# POWER.net
KiCad netlist of a schematic drawn in Altium Designer
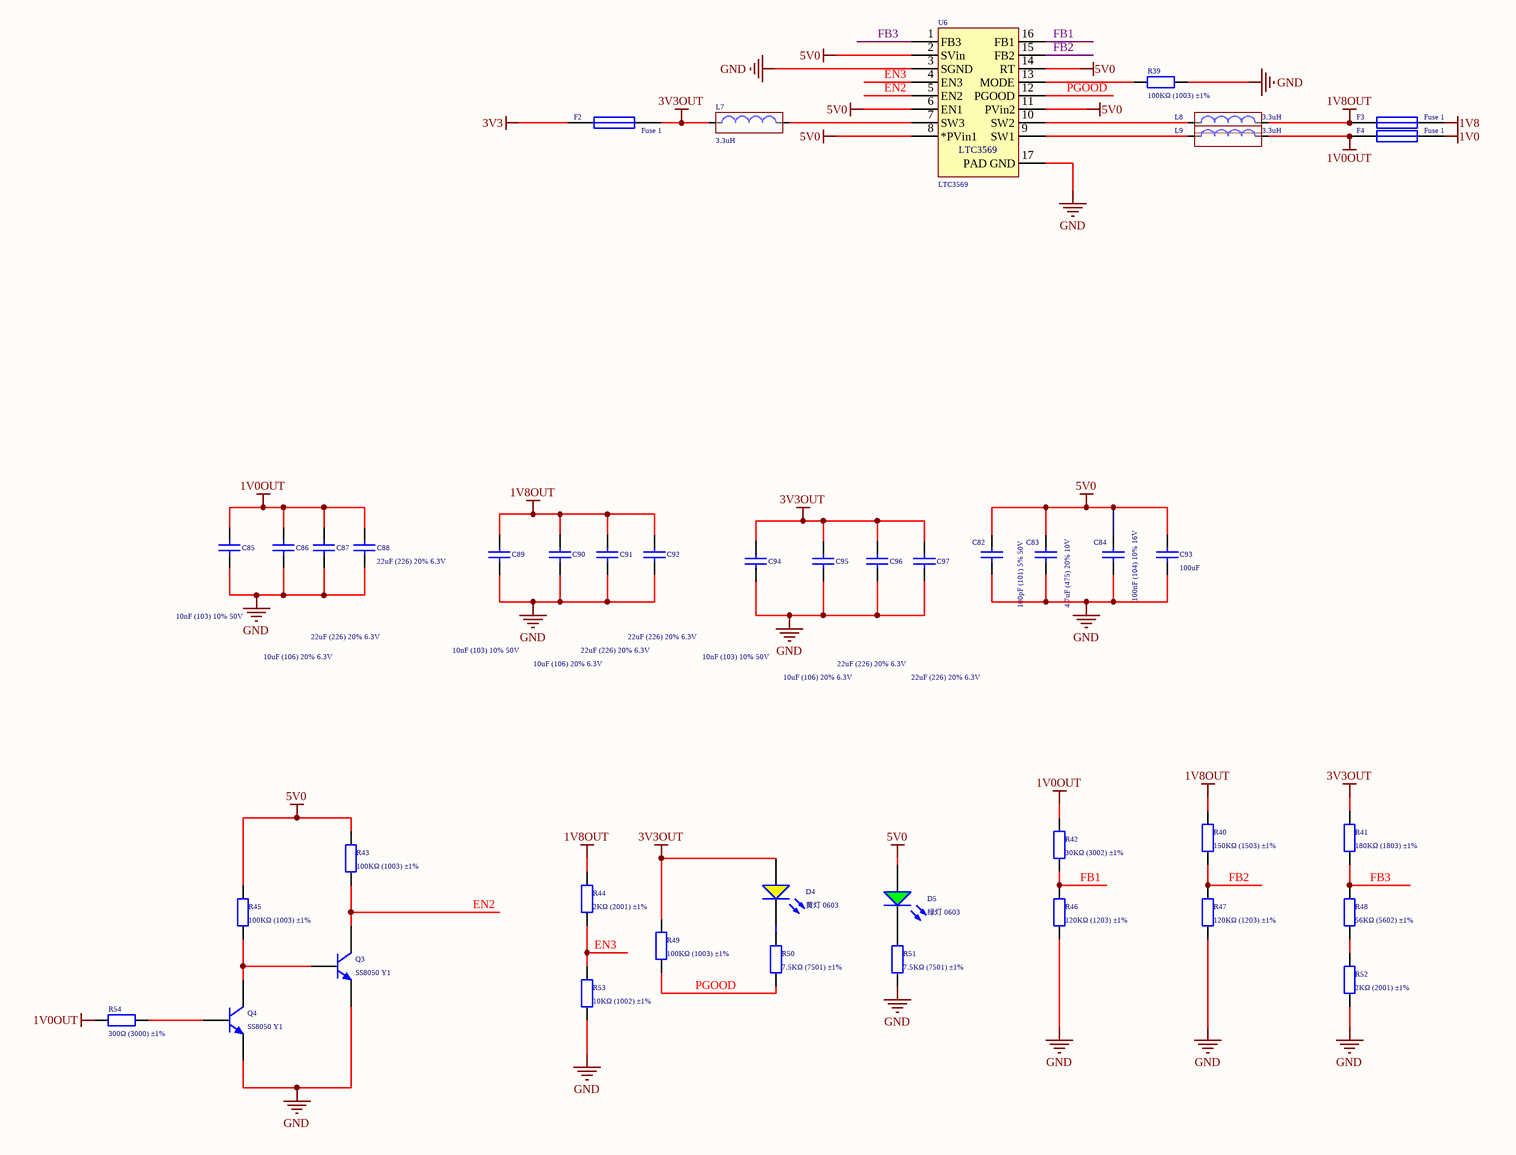
[diagram p0: POWER.SchDoc]

(export (version "E")
  (design (tool "Eeschema 10.0.6"))
  (components
    (comp (ref "C82")
      (value "100pF (101) 5% 50V")
      (footprint "0402_C")
      (description "贴片电容")
      (libsource (lib "Miscellaneous Devices LC") (part "0402 100pF (101) 5% 50V"))
    )
    (comp (ref "C83")
      (value "4.7uF (475) 20% 10V")
      (footprint "0402_C")
      (description "贴片电容")
      (libsource (lib "Miscellaneous Devices LC") (part "0402 4.7uF (475) 20% 10V"))
    )
    (comp (ref "C84")
      (value "100nF (104) 10% 16V")
      (footprint "0402_C")
      (description "贴片电容")
      (libsource (lib "Miscellaneous Devices LC") (part "0402 100nF (104) 10% 16V"))
    )
    (comp (ref "C85")
      (value "10nF (103) 10% 50V")
      (footprint "0402_C")
      (description "贴片电容")
      (libsource (lib "Miscellaneous Devices LC") (part "0402 10nF (103) 10% 50V"))
    )
    (comp (ref "C86")
      (value "10uF (106) 20% 6.3V")
      (footprint "0402_C")
      (description "贴片电容")
      (libsource (lib "Miscellaneous Devices LC") (part "0402 10uF (106) 20% 6.3V"))
    )
    (comp (ref "C87")
      (value "22uF (226) 20% 6.3V")
      (footprint "0603_C")
      (description "贴片电容")
      (libsource (lib "Miscellaneous Devices LC") (part "0603 22uF (226) 20% 6.3V"))
    )
    (comp (ref "C88")
      (value "22uF (226) 20% 6.3V")
      (footprint "0603_C")
      (description "贴片电容")
      (libsource (lib "Miscellaneous Devices LC") (part "0603 22uF (226) 20% 6.3V"))
    )
    (comp (ref "C89")
      (value "10nF (103) 10% 50V")
      (footprint "0402_C")
      (description "贴片电容")
      (libsource (lib "Miscellaneous Devices LC") (part "0402 10nF (103) 10% 50V"))
    )
    (comp (ref "C90")
      (value "10uF (106) 20% 6.3V")
      (footprint "0402_C")
      (description "贴片电容")
      (libsource (lib "Miscellaneous Devices LC") (part "0402 10uF (106) 20% 6.3V"))
    )
    (comp (ref "C91")
      (value "22uF (226) 20% 6.3V")
      (footprint "0603_C")
      (description "贴片电容")
      (libsource (lib "Miscellaneous Devices LC") (part "0603 22uF (226) 20% 6.3V"))
    )
    (comp (ref "C92")
      (value "22uF (226) 20% 6.3V")
      (footprint "0603_C")
      (description "贴片电容")
      (libsource (lib "Miscellaneous Devices LC") (part "0603 22uF (226) 20% 6.3V"))
    )
    (comp (ref "C93")
      (value "100uF")
      (footprint "LC-1206")
      (description "贴片电容")
      (fields (field (name "Comment") "Cap") (field (name "PUBLISHER") "Altium Limited"))
      (libsource (lib "Sparks") (part "Cap"))
    )
    (comp (ref "C94")
      (value "10nF (103) 10% 50V")
      (footprint "0402_C")
      (description "贴片电容")
      (libsource (lib "Miscellaneous Devices LC") (part "0402 10nF (103) 10% 50V"))
    )
    (comp (ref "C95")
      (value "10uF (106) 20% 6.3V")
      (footprint "0402_C")
      (description "贴片电容")
      (libsource (lib "Miscellaneous Devices LC") (part "0402 10uF (106) 20% 6.3V"))
    )
    (comp (ref "C96")
      (value "22uF (226) 20% 6.3V")
      (footprint "0603_C")
      (description "贴片电容")
      (libsource (lib "Miscellaneous Devices LC") (part "0603 22uF (226) 20% 6.3V"))
    )
    (comp (ref "C97")
      (value "22uF (226) 20% 6.3V")
      (footprint "0603_C")
      (description "贴片电容")
      (libsource (lib "Miscellaneous Devices LC") (part "0603 22uF (226) 20% 6.3V"))
    )
    (comp (ref "D4")
      (value "黄灯 0603")
      (footprint "0603_LED_S1")
      (description "发光二极管")
      (libsource (lib "Miscellaneous Devices LC") (part "0603 黄灯"))
    )
    (comp (ref "D5")
      (value "绿灯 0603")
      (footprint "0603_LED_S1")
      (description "发光二极管")
      (libsource (lib "Miscellaneous Devices LC") (part "0603 绿灯"))
    )
    (comp (ref "F2")
      (value "Fuse 1")
      (footprint "1206")
      (description "Fuse")
      (fields (field (name "PUBLISHER") "Altium Limited"))
      (libsource (lib "Miscellaneous Devices") (part "Fuse 1"))
    )
    (comp (ref "F3")
      (value "Fuse 1")
      (footprint "1206")
      (description "Fuse")
      (fields (field (name "PUBLISHER") "Altium Limited"))
      (libsource (lib "Miscellaneous Devices") (part "Fuse 1"))
    )
    (comp (ref "F4")
      (value "Fuse 1")
      (footprint "1206")
      (description "Fuse")
      (fields (field (name "PUBLISHER") "Altium Limited"))
      (libsource (lib "Miscellaneous Devices") (part "Fuse 1"))
    )
    (comp (ref "L7")
      (value "3.3uH")
      (footprint "LC-1210")
      (description "Inductor")
      (libsource (lib "2号库") (part "Inductor_1"))
    )
    (comp (ref "L8")
      (value "3.3uH")
      (footprint "LC-1210")
      (description "Inductor")
      (libsource (lib "2号库") (part "Inductor_1"))
    )
    (comp (ref "L9")
      (value "3.3uH")
      (footprint "LC-1210")
      (description "Inductor")
      (libsource (lib "2号库") (part "Inductor_1"))
    )
    (comp (ref "Q3")
      (value "SS8050 Y1")
      (footprint "SOT-23(SOT-23-3)")
      (description "三极管")
      (libsource (lib "Transistor_NPN") (part "SOT-23 SS8050 Y1"))
    )
    (comp (ref "Q4")
      (value "SS8050 Y1")
      (footprint "SOT-23(SOT-23-3)")
      (description "三极管")
      (libsource (lib "Transistor_NPN") (part "SOT-23 SS8050 Y1"))
    )
    (comp (ref "R39")
      (value "100KΩ (1003) ±1%")
      (footprint "0402_R")
      (description "贴片电阻")
      (libsource (lib "") (part "0402 100KΩ (1003) 1%_1"))
    )
    (comp (ref "R40")
      (value "150KΩ (1503) ±1%")
      (footprint "0402_R")
      (description "贴片电阻")
      (libsource (lib "Miscellaneous Devices LC") (part "0402 150KΩ (1503) 1%"))
    )
    (comp (ref "R41")
      (value "180KΩ (1803) ±1%")
      (footprint "0603_R")
      (description "贴片电阻")
      (libsource (lib "Miscellaneous Devices LC") (part "0603 180KΩ (1803) 1%"))
    )
    (comp (ref "R42")
      (value "30KΩ (3002) ±1%")
      (footprint "0603_R")
      (description "贴片电阻")
      (libsource (lib "RES") (part "0603 30KΩ (3002) 1%"))
    )
    (comp (ref "R43")
      (value "100KΩ (1003) ±1%")
      (footprint "0402_R")
      (description "贴片电阻")
      (libsource (lib "Miscellaneous Devices LC") (part "0402 100KΩ (1003) 1%"))
    )
    (comp (ref "R44")
      (value "2KΩ (2001) ±1%")
      (footprint "0402_R")
      (description "贴片电阻")
      (libsource (lib "Miscellaneous Devices LC") (part "0402 2KΩ (2001) 1%"))
    )
    (comp (ref "R45")
      (value "100KΩ (1003) ±1%")
      (footprint "0402_R")
      (description "贴片电阻")
      (libsource (lib "Miscellaneous Devices LC") (part "0402 100KΩ (1003) 1%"))
    )
    (comp (ref "R46")
      (value "120KΩ (1203) ±1%")
      (footprint "0402_R")
      (description "贴片电阻")
      (libsource (lib "Miscellaneous Devices LC") (part "0402 120KΩ (1203) 1%"))
    )
    (comp (ref "R47")
      (value "120KΩ (1203) ±1%")
      (footprint "0402_R")
      (description "贴片电阻")
      (libsource (lib "Miscellaneous Devices LC") (part "0402 120KΩ (1203) 1%"))
    )
    (comp (ref "R48")
      (value "56KΩ (5602) ±1%")
      (footprint "0402_R")
      (description "贴片电阻")
      (libsource (lib "Miscellaneous Devices LC") (part "0402 56KΩ (5602) 1%"))
    )
    (comp (ref "R49")
      (value "100KΩ (1003) ±1%")
      (footprint "0402_R")
      (description "贴片电阻")
      (libsource (lib "Miscellaneous Devices LC") (part "0402 100KΩ (1003) 1%"))
    )
    (comp (ref "R50")
      (value "7.5KΩ (7501) ±1%")
      (footprint "0402_R")
      (description "贴片电阻")
      (libsource (lib "Miscellaneous Devices LC") (part "0402 7.5KΩ (7501) 1%"))
    )
    (comp (ref "R51")
      (value "7.5KΩ (7501) ±1%")
      (footprint "0402_R")
      (description "贴片电阻")
      (libsource (lib "Miscellaneous Devices LC") (part "0402 7.5KΩ (7501) 1%"))
    )
    (comp (ref "R52")
      (value "2KΩ (2001) ±1%")
      (footprint "0402_R")
      (description "贴片电阻")
      (libsource (lib "Miscellaneous Devices LC") (part "0402 2KΩ (2001) 1%"))
    )
    (comp (ref "R53")
      (value "10KΩ (1002) ±1%")
      (footprint "0402_R")
      (description "贴片电阻")
      (libsource (lib "Miscellaneous Devices LC") (part "0402 10KΩ (1002) 1%"))
    )
    (comp (ref "R54")
      (value "300Ω (3000) ±1%")
      (footprint "0402_R")
      (description "贴片电阻")
      (libsource (lib "Miscellaneous Devices LC") (part "0402 300Ω (3000) 1%"))
    )
    (comp (ref "U6")
      (value "LTC3569")
      (footprint "SOP127P600-16N")
      (libsource (lib "Schlib") (part "LTC3569"))
    )
  )
  (nets
    (net (code "1") (name "/EN2") (class "Default")
      (node (ref "Q3") (pin "3") (pinfunction "C_3") (pintype "passive"))
      (node (ref "R43") (pin "1") (pinfunction "1_1") (pintype "passive"))
      (node (ref "U6") (pin "5") (pinfunction "EN2_5") (pintype "passive"))
    )
    (net (code "2") (name "/EN3") (class "Default")
      (node (ref "R44") (pin "1") (pinfunction "1_1") (pintype "passive"))
      (node (ref "R53") (pin "2") (pinfunction "2_2") (pintype "passive"))
      (node (ref "U6") (pin "4") (pinfunction "EN3_4") (pintype "passive"))
    )
    (net (code "3") (name "/FB1") (class "Default")
      (node (ref "R42") (pin "1") (pinfunction "1_1") (pintype "passive"))
      (node (ref "R46") (pin "2") (pinfunction "2_2") (pintype "passive"))
      (node (ref "U6") (pin "16") (pinfunction "FB1_16") (pintype "passive"))
    )
    (net (code "4") (name "/FB2") (class "Default")
      (node (ref "R40") (pin "1") (pinfunction "1_1") (pintype "passive"))
      (node (ref "R47") (pin "2") (pinfunction "2_2") (pintype "passive"))
      (node (ref "U6") (pin "15") (pinfunction "FB2_15") (pintype "passive"))
    )
    (net (code "5") (name "/FB3") (class "Default")
      (node (ref "R41") (pin "1") (pinfunction "1_1") (pintype "passive"))
      (node (ref "R48") (pin "2") (pinfunction "2_2") (pintype "passive"))
      (node (ref "U6") (pin "1") (pinfunction "FB3_1") (pintype "passive"))
    )
    (net (code "6") (name "/PGOOD") (class "Default")
      (node (ref "R49") (pin "1") (pinfunction "1_1") (pintype "passive"))
      (node (ref "R50") (pin "1") (pinfunction "1_1") (pintype "passive"))
      (node (ref "U6") (pin "12") (pinfunction "PGOOD_12") (pintype "passive"))
    )
    (net (code "7") (name "1V0") (class "Default")
      (node (ref "F4") (pin "1") (pinfunction "1_1") (pintype "passive"))
    )
    (net (code "8") (name "1V0OUT") (class "Default")
      (node (ref "C85") (pin "2") (pinfunction "2_2") (pintype "passive"))
      (node (ref "C86") (pin "2") (pinfunction "2_2") (pintype "passive"))
      (node (ref "C87") (pin "2") (pinfunction "2_2") (pintype "passive"))
      (node (ref "C88") (pin "2") (pinfunction "2_2") (pintype "passive"))
      (node (ref "F4") (pin "2") (pinfunction "2_2") (pintype "passive"))
      (node (ref "L9") (pin "2") (pinfunction "2_2") (pintype "passive"))
      (node (ref "R42") (pin "2") (pinfunction "2_2") (pintype "passive"))
      (node (ref "R54") (pin "1") (pinfunction "1_1") (pintype "passive"))
    )
    (net (code "9") (name "1V8") (class "Default")
      (node (ref "F3") (pin "1") (pinfunction "1_1") (pintype "passive"))
    )
    (net (code "10") (name "1V8OUT") (class "Default")
      (node (ref "C89") (pin "2") (pinfunction "2_2") (pintype "passive"))
      (node (ref "C90") (pin "2") (pinfunction "2_2") (pintype "passive"))
      (node (ref "C91") (pin "2") (pinfunction "2_2") (pintype "passive"))
      (node (ref "C92") (pin "2") (pinfunction "2_2") (pintype "passive"))
      (node (ref "F3") (pin "2") (pinfunction "2_2") (pintype "passive"))
      (node (ref "L8") (pin "2") (pinfunction "2_2") (pintype "passive"))
      (node (ref "R40") (pin "2") (pinfunction "2_2") (pintype "passive"))
      (node (ref "R44") (pin "2") (pinfunction "2_2") (pintype "passive"))
    )
    (net (code "11") (name "3V3") (class "Default")
      (node (ref "F2") (pin "2") (pinfunction "2_2") (pintype "passive"))
    )
    (net (code "12") (name "3V3OUT") (class "Default")
      (node (ref "C94") (pin "2") (pinfunction "2_2") (pintype "passive"))
      (node (ref "C95") (pin "2") (pinfunction "2_2") (pintype "passive"))
      (node (ref "C96") (pin "2") (pinfunction "2_2") (pintype "passive"))
      (node (ref "C97") (pin "2") (pinfunction "2_2") (pintype "passive"))
      (node (ref "D4") (pin "A") (pinfunction "A_A") (pintype "passive"))
      (node (ref "F2") (pin "1") (pinfunction "1_1") (pintype "passive"))
      (node (ref "L7") (pin "1") (pinfunction "1_1") (pintype "passive"))
      (node (ref "R41") (pin "2") (pinfunction "2_2") (pintype "passive"))
      (node (ref "R49") (pin "2") (pinfunction "2_2") (pintype "passive"))
    )
    (net (code "13") (name "5V0") (class "Default")
      (node (ref "C82") (pin "2") (pinfunction "2_2") (pintype "passive"))
      (node (ref "C83") (pin "1") (pinfunction "1_1") (pintype "passive"))
      (node (ref "C84") (pin "2") (pinfunction "2_2") (pintype "passive"))
      (node (ref "C93") (pin "2") (pinfunction "2_2") (pintype "passive"))
      (node (ref "D5") (pin "A") (pinfunction "A_A") (pintype "passive"))
      (node (ref "R43") (pin "2") (pinfunction "2_2") (pintype "passive"))
      (node (ref "R45") (pin "2") (pinfunction "2_2") (pintype "passive"))
      (node (ref "U6") (pin "11") (pinfunction "PVin2_11") (pintype "passive"))
      (node (ref "U6") (pin "14") (pinfunction "RT_14") (pintype "passive"))
      (node (ref "U6") (pin "2") (pinfunction "SVin_2") (pintype "passive"))
      (node (ref "U6") (pin "6") (pinfunction "EN1_6") (pintype "passive"))
      (node (ref "U6") (pin "8") (pinfunction "*PVin1_8") (pintype "passive"))
    )
    (net (code "14") (name "GND") (class "Default")
      (node (ref "C82") (pin "1") (pinfunction "1_1") (pintype "passive"))
      (node (ref "C83") (pin "2") (pinfunction "2_2") (pintype "passive"))
      (node (ref "C84") (pin "1") (pinfunction "1_1") (pintype "passive"))
      (node (ref "C85") (pin "1") (pinfunction "1_1") (pintype "passive"))
      (node (ref "C86") (pin "1") (pinfunction "1_1") (pintype "passive"))
      (node (ref "C87") (pin "1") (pinfunction "1_1") (pintype "passive"))
      (node (ref "C88") (pin "1") (pinfunction "1_1") (pintype "passive"))
      (node (ref "C89") (pin "1") (pinfunction "1_1") (pintype "passive"))
      (node (ref "C90") (pin "1") (pinfunction "1_1") (pintype "passive"))
      (node (ref "C91") (pin "1") (pinfunction "1_1") (pintype "passive"))
      (node (ref "C92") (pin "1") (pinfunction "1_1") (pintype "passive"))
      (node (ref "C93") (pin "1") (pinfunction "1_1") (pintype "passive"))
      (node (ref "C94") (pin "1") (pinfunction "1_1") (pintype "passive"))
      (node (ref "C95") (pin "1") (pinfunction "1_1") (pintype "passive"))
      (node (ref "C96") (pin "1") (pinfunction "1_1") (pintype "passive"))
      (node (ref "C97") (pin "1") (pinfunction "1_1") (pintype "passive"))
      (node (ref "Q3") (pin "2") (pinfunction "E_2") (pintype "passive"))
      (node (ref "Q4") (pin "2") (pinfunction "E_2") (pintype "passive"))
      (node (ref "R39") (pin "2") (pinfunction "2_2") (pintype "passive"))
      (node (ref "R46") (pin "1") (pinfunction "1_1") (pintype "passive"))
      (node (ref "R47") (pin "1") (pinfunction "1_1") (pintype "passive"))
      (node (ref "R51") (pin "1") (pinfunction "1_1") (pintype "passive"))
      (node (ref "R52") (pin "1") (pinfunction "1_1") (pintype "passive"))
      (node (ref "R53") (pin "1") (pinfunction "1_1") (pintype "passive"))
      (node (ref "U6") (pin "17") (pinfunction "PAD_GND_17") (pintype "passive"))
      (node (ref "U6") (pin "3") (pinfunction "SGND_3") (pintype "passive"))
    )
    (net (code "15") (name "Net-(D4-PadK)") (class "Default")
      (node (ref "D4") (pin "K") (pinfunction "K_K") (pintype "passive"))
      (node (ref "R50") (pin "2") (pinfunction "2_2") (pintype "passive"))
    )
    (net (code "16") (name "Net-(D5-PadK)") (class "Default")
      (node (ref "D5") (pin "K") (pinfunction "K_K") (pintype "passive"))
      (node (ref "R51") (pin "2") (pinfunction "2_2") (pintype "passive"))
    )
    (net (code "17") (name "Net-(Q3-B)") (class "Default")
      (node (ref "Q3") (pin "1") (pinfunction "B_1") (pintype "passive"))
      (node (ref "Q4") (pin "3") (pinfunction "C_3") (pintype "passive"))
      (node (ref "R45") (pin "1") (pinfunction "1_1") (pintype "passive"))
    )
    (net (code "18") (name "Net-(Q4-B)") (class "Default")
      (node (ref "Q4") (pin "1") (pinfunction "B_1") (pintype "passive"))
      (node (ref "R54") (pin "2") (pinfunction "2_2") (pintype "passive"))
    )
    (net (code "19") (name "Net-(R48-Pad1)") (class "Default")
      (node (ref "R48") (pin "1") (pinfunction "1_1") (pintype "passive"))
      (node (ref "R52") (pin "2") (pinfunction "2_2") (pintype "passive"))
    )
    (net (code "20") (name "Net-(U6-MODE)") (class "Default")
      (node (ref "R39") (pin "1") (pinfunction "1_1") (pintype "passive"))
      (node (ref "U6") (pin "13") (pinfunction "MODE_13") (pintype "passive"))
    )
    (net (code "21") (name "Net-(U6-SW1)") (class "Default")
      (node (ref "L9") (pin "1") (pinfunction "1_1") (pintype "passive"))
      (node (ref "U6") (pin "9") (pinfunction "SW1_9") (pintype "passive"))
    )
    (net (code "22") (name "Net-(U6-SW2)") (class "Default")
      (node (ref "L8") (pin "1") (pinfunction "1_1") (pintype "passive"))
      (node (ref "U6") (pin "10") (pinfunction "SW2_10") (pintype "passive"))
    )
    (net (code "23") (name "Net-(U6-SW3)") (class "Default")
      (node (ref "L7") (pin "2") (pinfunction "2_2") (pintype "passive"))
      (node (ref "U6") (pin "7") (pinfunction "SW3_7") (pintype "passive"))
    )
  )
)
